# utilidong-lipo-charger-mk-2_2.net
KiCad netlist of a schematic drawn in EAGLE
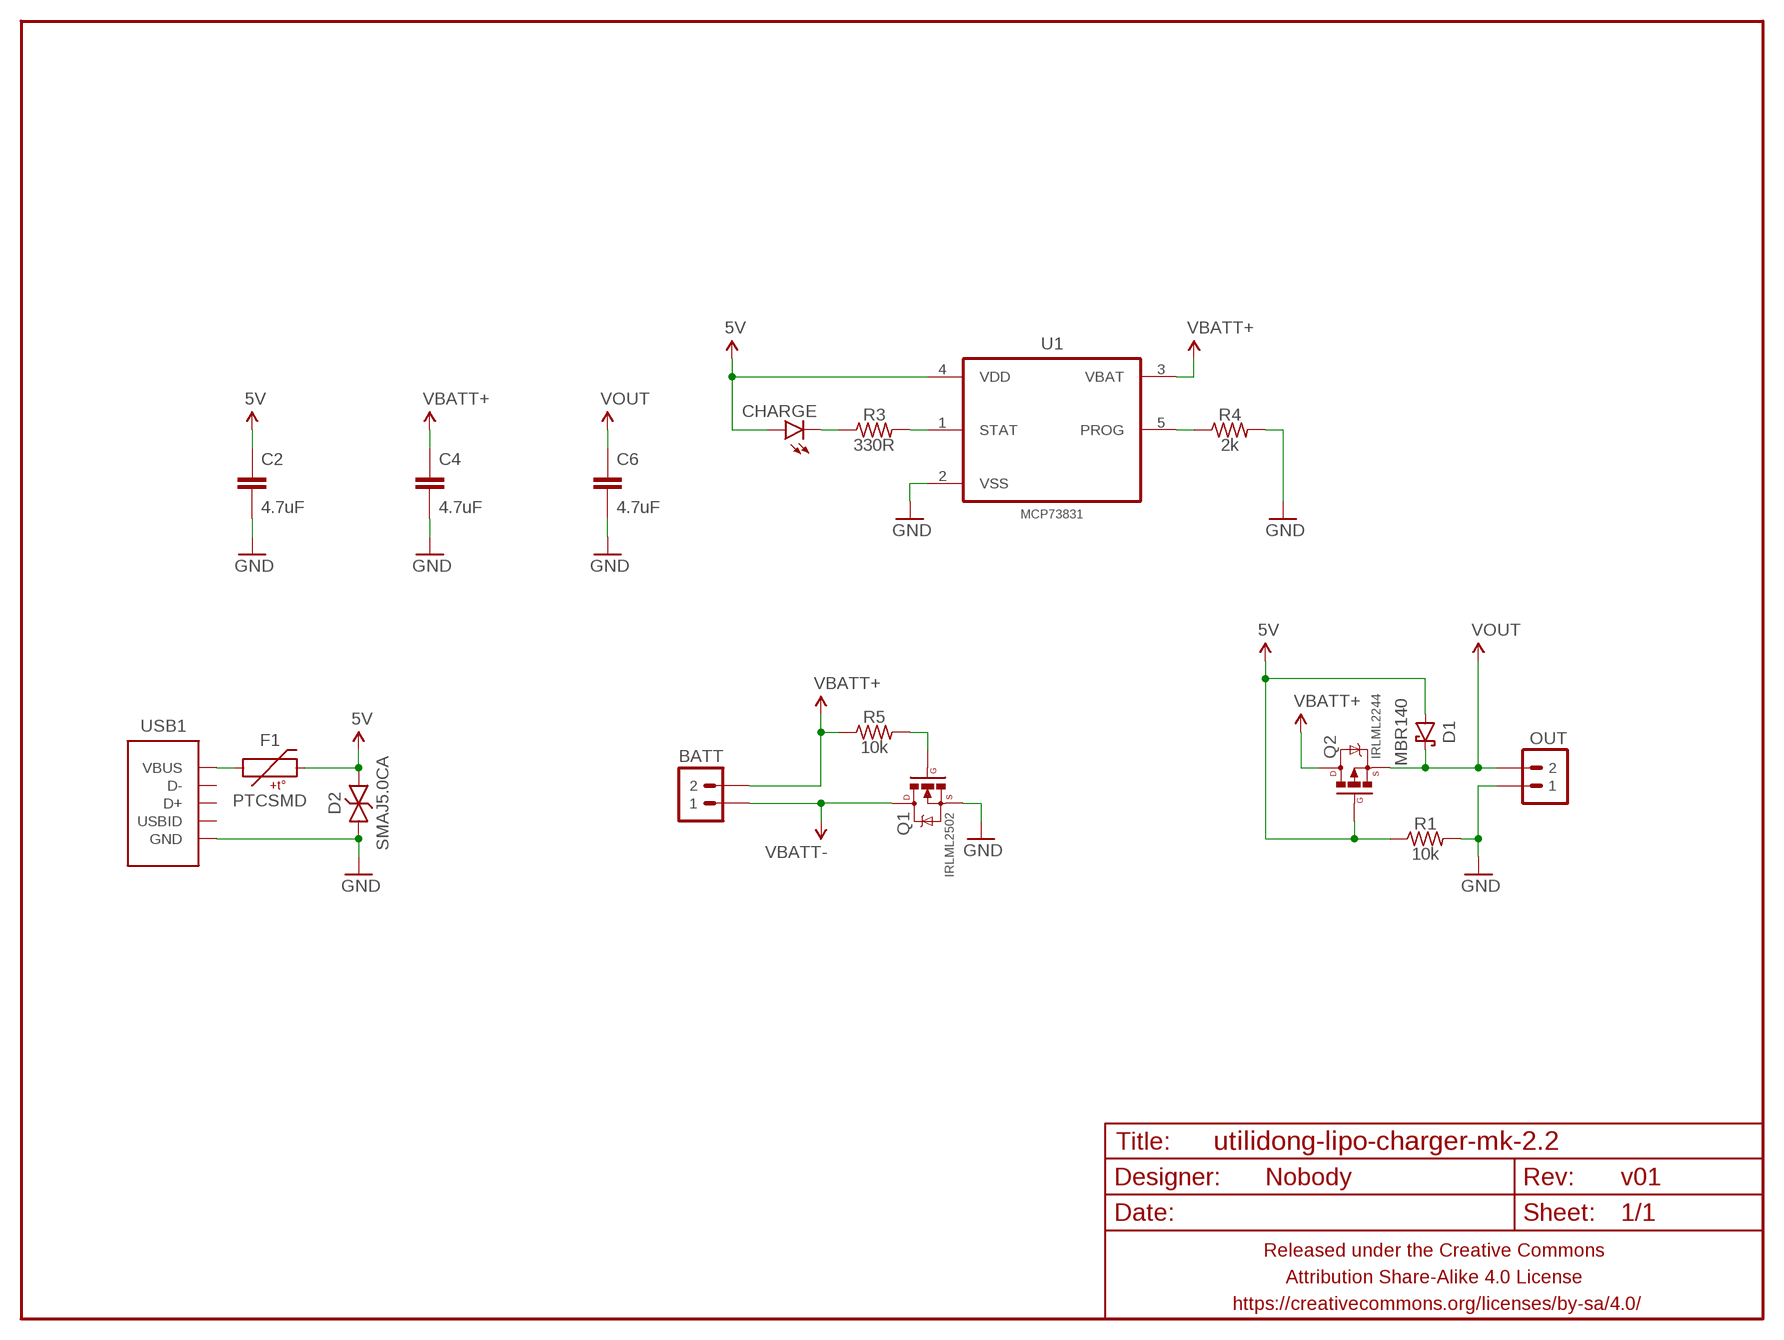
[diagram p0: schematic, sheet 1]

(export (version "E")
  (design (tool "Eeschema 10.0.6"))
  (components
    (comp (ref "BATT")
      (value "M02PTH-CENTERED-R+")
      (footprint "eagle-import:1X02-CENTER-R+")
      (libsource (lib "eagle-import") (part "M02PTH-CENTERED-R+"))
    )
    (comp (ref "C2")
      (value "4.7uF")
      (footprint "eagle-import:C0603")
      (libsource (lib "eagle-import") (part "CAPACITOR-CERAMICC0603"))
    )
    (comp (ref "C4")
      (value "4.7uF")
      (footprint "eagle-import:C0603")
      (libsource (lib "eagle-import") (part "CAPACITOR-CERAMICC0603"))
    )
    (comp (ref "C6")
      (value "4.7uF")
      (footprint "eagle-import:C0603")
      (libsource (lib "eagle-import") (part "CAPACITOR-CERAMICC0603"))
    )
    (comp (ref "CHARGE")
      (value "LED1206")
      (footprint "eagle-import:LED-1206")
      (libsource (lib "eagle-import") (part "LED1206"))
    )
    (comp (ref "D1")
      (value "MBR140")
      (footprint "eagle-import:SMA-DIODE-SCHOTTKY")
      (libsource (lib "eagle-import") (part "DIODE-SCHOTTKYSMA"))
    )
    (comp (ref "D2")
      (value "SMAJ5.0CA")
      (footprint "eagle-import:SMA-DIODE-TVS-BIDIR")
      (libsource (lib "eagle-import") (part "TVSSMA"))
    )
    (comp (ref "F1")
      (value "PTCSMD")
      (footprint "eagle-import:PTC-1206")
      (libsource (lib "eagle-import") (part "PTCSMD"))
    )
    (comp (ref "FRAME1")
      (value "FRAME-LETTERNO_PACKAGE")
      (footprint "eagle-import:DUMMY")
      (fields (field (name "DESIGNER") "Nobody"))
      (libsource (lib "eagle-import") (part "FRAME-LETTERNO_PACKAGE"))
    )
    (comp (ref "OUT")
      (value "M02PTH-CENTERED-R+")
      (footprint "eagle-import:1X02-CENTER-R+")
      (libsource (lib "eagle-import") (part "M02PTH-CENTERED-R+"))
    )
    (comp (ref "Q1")
      (value "IRLML2502")
      (footprint "eagle-import:SOT23")
      (libsource (lib "eagle-import") (part "MOSFET-NCHANNELBSS138"))
    )
    (comp (ref "Q2")
      (value "IRLML2244")
      (footprint "eagle-import:SOT23-3")
      (libsource (lib "eagle-import") (part "MOSFET-PCHANNELIRLML2244"))
    )
    (comp (ref "R1")
      (value "10k")
      (footprint "eagle-import:R0603")
      (libsource (lib "eagle-import") (part "RESISTORR0603"))
    )
    (comp (ref "R3")
      (value "330R")
      (footprint "eagle-import:R0603")
      (libsource (lib "eagle-import") (part "RESISTORR0603"))
    )
    (comp (ref "R4")
      (value "2k")
      (footprint "eagle-import:R0603")
      (libsource (lib "eagle-import") (part "RESISTORR0603"))
    )
    (comp (ref "R5")
      (value "10k")
      (footprint "eagle-import:R0603")
      (libsource (lib "eagle-import") (part "RESISTORR0603"))
    )
    (comp (ref "U1")
      (value "MCP73831")
      (footprint "eagle-import:SOT95P280X145-5N")
      (fields (field (name "MPN") "MCP73831T-2ACI/OT"))
      (libsource (lib "eagle-import") (part "MCP73831T-2ACI/OT"))
    )
    (comp (ref "USB1")
      (value "USB-ABCOMBO")
      (footprint "eagle-import:USB-MICRO-B-FCI-CUTOUT")
      (libsource (lib "eagle-import") (part "USB-ABCOMBO"))
    )
  )
  (nets
    (net (code "1") (name "5V") (class "Default")
      (node (ref "C2") (pin "1") (pinfunction "1_1") (pintype "passive"))
      (node (ref "CHARGE") (pin "A") (pinfunction "A_A") (pintype "passive"))
      (node (ref "D1") (pin "A") (pinfunction "A_A") (pintype "passive"))
      (node (ref "D2") (pin "2") (pinfunction "2_2") (pintype "passive"))
      (node (ref "F1") (pin "2") (pinfunction "2_2") (pintype "passive"))
      (node (ref "Q2") (pin "1") (pinfunction "G_1") (pintype "passive"))
      (node (ref "R1") (pin "1") (pinfunction "1_1") (pintype "passive"))
      (node (ref "U1") (pin "4") (pinfunction "VDD_4") (pintype "power_in"))
    )
    (net (code "2") (name "GND") (class "Default")
      (node (ref "C2") (pin "2") (pinfunction "2_2") (pintype "passive"))
      (node (ref "C4") (pin "2") (pinfunction "2_2") (pintype "passive"))
      (node (ref "C6") (pin "2") (pinfunction "2_2") (pintype "passive"))
      (node (ref "D2") (pin "1") (pinfunction "1_1") (pintype "passive"))
      (node (ref "OUT") (pin "1") (pinfunction "1_1") (pintype "passive"))
      (node (ref "Q1") (pin "2") (pinfunction "S_2") (pintype "passive"))
      (node (ref "R1") (pin "2") (pinfunction "2_2") (pintype "passive"))
      (node (ref "R4") (pin "2") (pinfunction "2_2") (pintype "passive"))
      (node (ref "U1") (pin "2") (pinfunction "VSS_2") (pintype "power_in"))
      (node (ref "USB1") (pin "5") (pinfunction "GND_5") (pintype "bidirectional"))
      (node (ref "USB1") (pin "P$1") (pinfunction "GND_P$1") (pintype "bidirectional"))
      (node (ref "USB1") (pin "P$2") (pinfunction "GND_P$2") (pintype "bidirectional"))
    )
    (net (code "3") (name "Net-(CHARGE-PadC)") (class "Default")
      (node (ref "CHARGE") (pin "C") (pinfunction "C_C") (pintype "passive"))
      (node (ref "R3") (pin "1") (pinfunction "1_1") (pintype "passive"))
    )
    (net (code "4") (name "Net-(Q1-G)") (class "Default")
      (node (ref "Q1") (pin "1") (pinfunction "G_1") (pintype "passive"))
      (node (ref "R5") (pin "2") (pinfunction "2_2") (pintype "passive"))
    )
    (net (code "5") (name "Net-(U1-PROG)") (class "Default")
      (node (ref "R4") (pin "1") (pinfunction "1_1") (pintype "passive"))
      (node (ref "U1") (pin "5") (pinfunction "PROG_5") (pintype "input"))
    )
    (net (code "6") (name "Net-(U1-STAT)") (class "Default")
      (node (ref "R3") (pin "2") (pinfunction "2_2") (pintype "passive"))
      (node (ref "U1") (pin "1") (pinfunction "STAT_1") (pintype "output"))
    )
    (net (code "7") (name "Net-(USB1-VBUS)") (class "Default")
      (node (ref "F1") (pin "1") (pinfunction "1_1") (pintype "passive"))
      (node (ref "USB1") (pin "1") (pinfunction "VBUS_1") (pintype "bidirectional"))
    )
    (net (code "8") (name "VBATT+") (class "Default")
      (node (ref "BATT") (pin "2") (pinfunction "2_2") (pintype "passive"))
      (node (ref "C4") (pin "1") (pinfunction "1_1") (pintype "passive"))
      (node (ref "Q2") (pin "3") (pinfunction "D_3") (pintype "passive"))
      (node (ref "R5") (pin "1") (pinfunction "1_1") (pintype "passive"))
      (node (ref "U1") (pin "3") (pinfunction "VBAT_3") (pintype "output"))
    )
    (net (code "9") (name "VBATT-") (class "Default")
      (node (ref "BATT") (pin "1") (pinfunction "1_1") (pintype "passive"))
      (node (ref "Q1") (pin "3") (pinfunction "D_3") (pintype "passive"))
    )
    (net (code "10") (name "VOUT") (class "Default")
      (node (ref "C6") (pin "1") (pinfunction "1_1") (pintype "passive"))
      (node (ref "D1") (pin "C") (pinfunction "C_C") (pintype "passive"))
      (node (ref "OUT") (pin "2") (pinfunction "2_2") (pintype "passive"))
      (node (ref "Q2") (pin "2") (pinfunction "S_2") (pintype "passive"))
    )
    (net (code "11") (name "unconnected-(USB1-D+-Pad3)") (class "Default")
      (node (ref "USB1") (pin "3") (pinfunction "D+_3") (pintype "bidirectional"))
    )
    (net (code "12") (name "unconnected-(USB1-D--Pad2)") (class "Default")
      (node (ref "USB1") (pin "2") (pinfunction "D-_2") (pintype "bidirectional"))
    )
    (net (code "13") (name "unconnected-(USB1-USBID-Pad4)") (class "Default")
      (node (ref "USB1") (pin "4") (pinfunction "USBID_4") (pintype "bidirectional"))
    )
  )
)
